# Connectors.net
KiCad netlist of a schematic drawn in Altium Designer
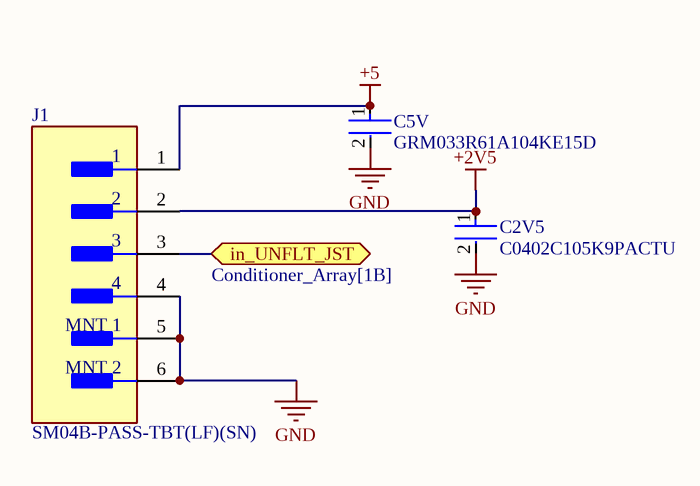
[diagram p0: Connectors.SchDoc]

(export (version "E")
  (design (tool "Eeschema 10.0.6"))
  (components
    (comp (ref "C2V5")
      (value "C0402C105K9PACTU")
      (footprint "FP-C0402C105K9PACTU-MFG")
      (description "CAP CER 1UF 6.3V X5R 0402")
      (fields (field (name "TOLERANCE") "10%") (field (name "VOLTAGE") "6.3V"))
      (libsource (lib "Altium Content Vault") (part "11868f565c42a9108669ba33697ecf6"))
    )
    (comp (ref "C5V")
      (value "GRM033R61A104KE15D")
      (footprint "FP-GRM033-0_03-IPC_C")
      (description "Chip Multilayer Ceramic Capacitors for General Purpose, 0201, 0.10uF, X5R, 15%, 10%, 10V")
      (fields (field (name "TOLERANCE") "10%") (field (name "VOLTAGE") "10V"))
      (libsource (lib "Altium Content Vault") (part "b4654b650e69147ec39a6b967a45e02"))
    )
    (comp (ref "J1")
      (value "SM04B-PASS-TBT(LF)(SN)")
      (footprint "FP-SM04B-PASS-TBT_LF_SN-MFG")
      (description "CONN HEADER SMD R/A 4POS 2MM")
      (fields
        (field (name "MANUFACTURER") "JST")
        (field (name "OCTOPART") "https://octopart.com/sm04b-pass-tbt%28lf%29%28sn%29-jst-3990422")
      )
      (libsource (lib "Altium Content Vault") (part "8e3688c4b118bffc0dd9b7401e414ba"))
    )
  )
  (nets
    (net (code "1") (name "+2V5") (class "Default")
      (node (ref "C2V5") (pin "1") (pinfunction "1_1") (pintype "passive"))
      (node (ref "J1") (pin "2") (pinfunction "2_2") (pintype "passive"))
    )
    (net (code "2") (name "+5") (class "Default")
      (node (ref "C5V") (pin "1") (pinfunction "1_1") (pintype "passive"))
      (node (ref "J1") (pin "1") (pinfunction "1_1") (pintype "passive"))
    )
    (net (code "3") (name "/in_UNFLT_JST") (class "Default")
      (node (ref "J1") (pin "3") (pinfunction "3_3") (pintype "passive"))
    )
    (net (code "4") (name "GND") (class "Default")
      (node (ref "C2V5") (pin "2") (pinfunction "2_2") (pintype "passive"))
      (node (ref "C5V") (pin "2") (pinfunction "2_2") (pintype "passive"))
      (node (ref "J1") (pin "4") (pinfunction "4_4") (pintype "passive"))
      (node (ref "J1") (pin "5") (pinfunction "MNT_1_5") (pintype "passive"))
      (node (ref "J1") (pin "6") (pinfunction "MNT_2_6") (pintype "passive"))
    )
  )
)
